# Transimpedance_Amplifier.net
KiCad netlist of a schematic drawn in Altium Designer
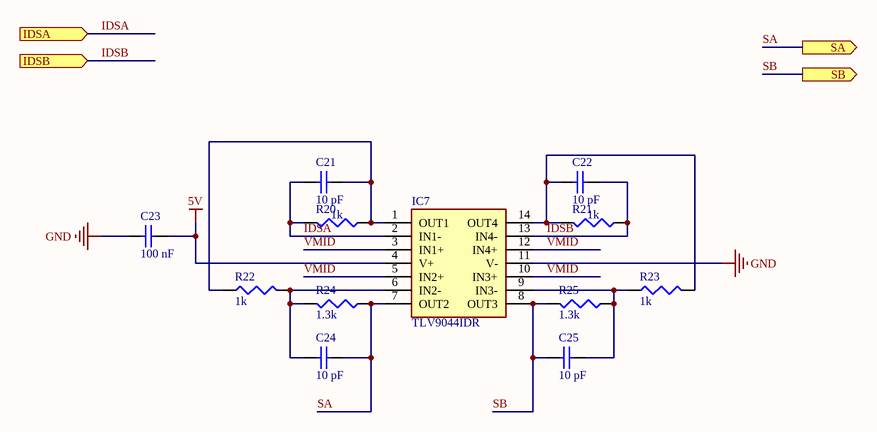
[diagram p0: Transimpedance_Amplifier.SchDoc]

(export (version "E")
  (design (tool "Eeschema 10.0.6"))
  (components
    (comp (ref "C21")
      (value "10 pF")
      (footprint "1608[0603]")
      (fields (field (name "PUBLISHER") "Altium Limited"))
      (libsource (lib "Miscellaneous Devices") (part "Cap Semi"))
    )
    (comp (ref "C22")
      (value "10 pF")
      (footprint "1608[0603]")
      (fields (field (name "PUBLISHER") "Altium Limited"))
      (libsource (lib "Miscellaneous Devices") (part "Cap Semi"))
    )
    (comp (ref "C23")
      (value "100 nF")
      (footprint "1608[0603]")
      (fields (field (name "PUBLISHER") "Altium Limited"))
      (libsource (lib "Miscellaneous Devices") (part "Cap Semi"))
    )
    (comp (ref "C24")
      (value "10 pF")
      (footprint "1608[0603]")
      (fields (field (name "PUBLISHER") "Altium Limited"))
      (libsource (lib "Miscellaneous Devices") (part "Cap Semi"))
    )
    (comp (ref "C25")
      (value "10 pF")
      (footprint "1608[0603]")
      (fields (field (name "PUBLISHER") "Altium Limited"))
      (libsource (lib "Miscellaneous Devices") (part "Cap Semi"))
    )
    (comp (ref "IC7")
      (value "TLV9044IDR")
      (footprint "SamacSys:SOIC127P600X175-14N")
      (description "Integrated Circuit")
      (fields (field (name "MOUSER PART NUMBER") "595-TLV9044IDR"))
      (libsource (lib "SamacSys") (part "TLV9044IDR"))
    )
    (comp (ref "R20")
      (value "1k")
      (footprint "J1-0603")
      (description "Resistor")
      (fields (field (name "PUBLISHER") "Altium Limited"))
      (libsource (lib "Miscellaneous Devices") (part "Res3"))
    )
    (comp (ref "R21")
      (value "1k")
      (footprint "J1-0603")
      (description "Resistor")
      (fields (field (name "PUBLISHER") "Altium Limited"))
      (libsource (lib "Miscellaneous Devices") (part "Res3"))
    )
    (comp (ref "R22")
      (value "1k")
      (footprint "J1-0603")
      (description "Resistor")
      (fields (field (name "PUBLISHER") "Altium Limited"))
      (libsource (lib "Miscellaneous Devices") (part "Res3"))
    )
    (comp (ref "R23")
      (value "1k")
      (footprint "J1-0603")
      (description "Resistor")
      (fields (field (name "PUBLISHER") "Altium Limited"))
      (libsource (lib "Miscellaneous Devices") (part "Res3"))
    )
    (comp (ref "R24")
      (value "1.3k")
      (footprint "J1-0603")
      (description "Resistor")
      (fields (field (name "PUBLISHER") "Altium Limited"))
      (libsource (lib "Miscellaneous Devices") (part "Res3"))
    )
    (comp (ref "R25")
      (value "1.3k")
      (footprint "J1-0603")
      (description "Resistor")
      (fields (field (name "PUBLISHER") "Altium Limited"))
      (libsource (lib "Miscellaneous Devices") (part "Res3"))
    )
  )
  (nets
    (net (code "1") (name "/IDSA") (class "Default")
      (node (ref "C21") (pin "1") (pinfunction "1_1") (pintype "passive"))
      (node (ref "IC7") (pin "2") (pinfunction "IN1-_2") (pintype "passive"))
      (node (ref "R20") (pin "2") (pinfunction "2_2") (pintype "passive"))
    )
    (net (code "2") (name "/IDSB") (class "Default")
      (node (ref "C22") (pin "2") (pinfunction "2_2") (pintype "passive"))
      (node (ref "IC7") (pin "13") (pinfunction "IN4-_13") (pintype "passive"))
      (node (ref "R21") (pin "1") (pinfunction "1_1") (pintype "passive"))
    )
    (net (code "3") (name "/SA") (class "Default")
      (node (ref "C24") (pin "2") (pinfunction "2_2") (pintype "passive"))
      (node (ref "IC7") (pin "7") (pinfunction "OUT2_7") (pintype "passive"))
      (node (ref "R24") (pin "1") (pinfunction "1_1") (pintype "passive"))
    )
    (net (code "4") (name "/SB") (class "Default")
      (node (ref "C25") (pin "1") (pinfunction "1_1") (pintype "passive"))
      (node (ref "IC7") (pin "8") (pinfunction "OUT3_8") (pintype "passive"))
      (node (ref "R25") (pin "2") (pinfunction "2_2") (pintype "passive"))
    )
    (net (code "5") (name "/VMID") (class "Default")
      (node (ref "IC7") (pin "10") (pinfunction "IN3+_10") (pintype "passive"))
      (node (ref "IC7") (pin "12") (pinfunction "IN4+_12") (pintype "passive"))
      (node (ref "IC7") (pin "3") (pinfunction "IN1+_3") (pintype "passive"))
      (node (ref "IC7") (pin "5") (pinfunction "IN2+_5") (pintype "passive"))
    )
    (net (code "6") (name "5V") (class "Default")
      (node (ref "C23") (pin "2") (pinfunction "2_2") (pintype "passive"))
      (node (ref "IC7") (pin "4") (pinfunction "V+_4") (pintype "passive"))
    )
    (net (code "7") (name "GND") (class "Default")
      (node (ref "C23") (pin "1") (pinfunction "1_1") (pintype "passive"))
      (node (ref "IC7") (pin "11") (pinfunction "V-_11") (pintype "passive"))
    )
    (net (code "8") (name "Net-(IC7-IN2-)") (class "Default")
      (node (ref "C24") (pin "1") (pinfunction "1_1") (pintype "passive"))
      (node (ref "IC7") (pin "6") (pinfunction "IN2-_6") (pintype "passive"))
      (node (ref "R22") (pin "2") (pinfunction "2_2") (pintype "passive"))
      (node (ref "R24") (pin "2") (pinfunction "2_2") (pintype "passive"))
    )
    (net (code "9") (name "Net-(IC7-IN3-)") (class "Default")
      (node (ref "C25") (pin "2") (pinfunction "2_2") (pintype "passive"))
      (node (ref "IC7") (pin "9") (pinfunction "IN3-_9") (pintype "passive"))
      (node (ref "R23") (pin "1") (pinfunction "1_1") (pintype "passive"))
      (node (ref "R25") (pin "1") (pinfunction "1_1") (pintype "passive"))
    )
    (net (code "10") (name "Net-(IC7-OUT1)") (class "Default")
      (node (ref "C21") (pin "2") (pinfunction "2_2") (pintype "passive"))
      (node (ref "IC7") (pin "1") (pinfunction "OUT1_1") (pintype "passive"))
      (node (ref "R20") (pin "1") (pinfunction "1_1") (pintype "passive"))
      (node (ref "R22") (pin "1") (pinfunction "1_1") (pintype "passive"))
    )
    (net (code "11") (name "Net-(IC7-OUT4)") (class "Default")
      (node (ref "C22") (pin "1") (pinfunction "1_1") (pintype "passive"))
      (node (ref "IC7") (pin "14") (pinfunction "OUT4_14") (pintype "passive"))
      (node (ref "R21") (pin "2") (pinfunction "2_2") (pintype "passive"))
      (node (ref "R23") (pin "2") (pinfunction "2_2") (pintype "passive"))
    )
  )
)
